# uart_izol.net
KiCad netlist of a schematic drawn in EAGLE
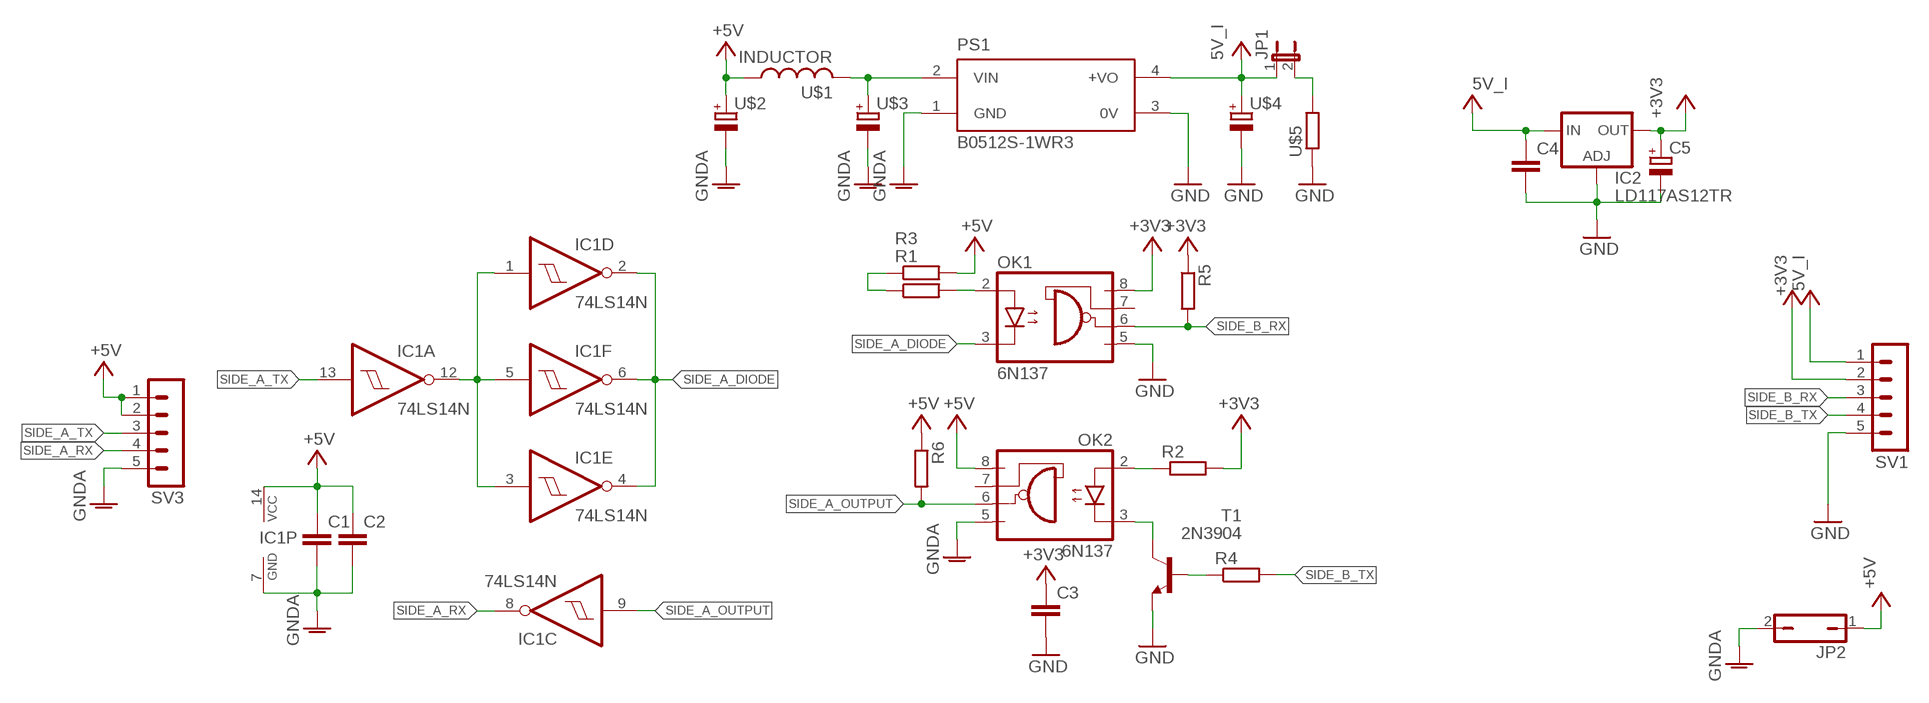
[diagram p0: schematic, sheet 1]

(export (version "E")
  (design (tool "Eeschema 10.0.6"))
  (components
    (comp (ref "C1")
      (value "C-EUC0805")
      (footprint "eagle-import:C0805")
      (libsource (lib "eagle-import") (part "C-EUC0805"))
    )
    (comp (ref "C2")
      (value "C-EUC0805")
      (footprint "eagle-import:C0805")
      (libsource (lib "eagle-import") (part "C-EUC0805"))
    )
    (comp (ref "C3")
      (value "C-EUC0805")
      (footprint "eagle-import:C0805")
      (libsource (lib "eagle-import") (part "C-EUC0805"))
    )
    (comp (ref "C4")
      (value "C-EUC0805")
      (footprint "eagle-import:C0805")
      (libsource (lib "eagle-import") (part "C-EUC0805"))
    )
    (comp (ref "C5")
      (value "CPOL-EUSMCB")
      (footprint "eagle-import:SMC_B")
      (libsource (lib "eagle-import") (part "CPOL-EUSMCB"))
    )
    (comp (ref "IC1")
      (value "74LS14N")
      (footprint "eagle-import:DIL14")
      (libsource (lib "eagle-import") (part "7414NLS"))
    )
    (comp (ref "IC2")
      (value "LD117AS12TR")
      (footprint "eagle-import:SOT223")
      (libsource (lib "eagle-import") (part "LD117A?S12TR"))
    )
    (comp (ref "JP1")
      (value "JP1E")
      (footprint "eagle-import:JP1")
      (libsource (lib "eagle-import") (part "JP1E"))
    )
    (comp (ref "JP2")
      (value "JP1Q")
      (footprint "eagle-import:JP1")
      (libsource (lib "eagle-import") (part "JP1Q"))
    )
    (comp (ref "OK1")
      (value "6N137")
      (footprint "eagle-import:DIL08")
      (libsource (lib "eagle-import") (part "6N137"))
    )
    (comp (ref "OK2")
      (value "6N137")
      (footprint "eagle-import:DIL08")
      (libsource (lib "eagle-import") (part "6N137"))
    )
    (comp (ref "PS1")
      (value "B0512S-1WR3")
      (footprint "eagle-import:CONV_B0512S-1WR3")
      (fields (field (name "MF") "Mornsun America, LLC"))
      (libsource (lib "eagle-import") (part "B0512S-1WR3"))
    )
    (comp (ref "R1")
      (value "R-EU_M0805")
      (footprint "eagle-import:M0805")
      (libsource (lib "eagle-import") (part "R-EU_M0805"))
    )
    (comp (ref "R2")
      (value "R-EU_M0805")
      (footprint "eagle-import:M0805")
      (libsource (lib "eagle-import") (part "R-EU_M0805"))
    )
    (comp (ref "R3")
      (value "R-EU_M0805")
      (footprint "eagle-import:M0805")
      (libsource (lib "eagle-import") (part "R-EU_M0805"))
    )
    (comp (ref "R4")
      (value "R-EU_M0805")
      (footprint "eagle-import:M0805")
      (libsource (lib "eagle-import") (part "R-EU_M0805"))
    )
    (comp (ref "R5")
      (value "R-EU_M0805")
      (footprint "eagle-import:M0805")
      (libsource (lib "eagle-import") (part "R-EU_M0805"))
    )
    (comp (ref "R6")
      (value "R-EU_M0805")
      (footprint "eagle-import:M0805")
      (libsource (lib "eagle-import") (part "R-EU_M0805"))
    )
    (comp (ref "SV1")
      (value "MA05-1")
      (footprint "eagle-import:MA05-1")
      (libsource (lib "eagle-import") (part "MA05-1"))
    )
    (comp (ref "SV3")
      (value "MA05-1")
      (footprint "eagle-import:MA05-1")
      (libsource (lib "eagle-import") (part "MA05-1"))
    )
    (comp (ref "T1")
      (value "2N3904")
      (footprint "eagle-import:TO92")
      (libsource (lib "eagle-import") (part "2N3904"))
    )
    (comp (ref "U$1")
      (value "INDUCTOR")
      (footprint "eagle-import:0207_10")
      (libsource (lib "eagle-import") (part "INDUCTOR"))
    )
    (comp (ref "U$2")
      (value "CAPACITOR")
      (footprint "eagle-import:E2,5-7")
      (libsource (lib "eagle-import") (part "CAPACITOR"))
    )
    (comp (ref "U$3")
      (value "CAPACITOR")
      (footprint "eagle-import:E2,5-7")
      (libsource (lib "eagle-import") (part "CAPACITOR"))
    )
    (comp (ref "U$4")
      (value "CAPACITOR")
      (footprint "eagle-import:E2,5-7")
      (libsource (lib "eagle-import") (part "CAPACITOR"))
    )
    (comp (ref "U$5")
      (value "RESISTOR")
      (footprint "eagle-import:0207_10")
      (libsource (lib "eagle-import") (part "RESISTOR"))
    )
  )
  (nets
    (net (code "1") (name "+3V3") (class "Default")
      (node (ref "C3") (pin "1") (pinfunction "1_1") (pintype "passive"))
      (node (ref "C5") (pin "+") (pinfunction "+_+") (pintype "passive"))
      (node (ref "IC2") (pin "4") (pinfunction "OUT_4") (pintype "passive"))
      (node (ref "OK1") (pin "8") (pinfunction "VCC_8") (pintype "passive"))
      (node (ref "R2") (pin "2") (pinfunction "2_2") (pintype "passive"))
      (node (ref "R5") (pin "1") (pinfunction "1_1") (pintype "passive"))
      (node (ref "SV1") (pin "2") (pinfunction "2_2") (pintype "passive"))
    )
    (net (code "2") (name "+5V") (class "Default")
      (node (ref "C1") (pin "1") (pinfunction "1_1") (pintype "passive"))
      (node (ref "C2") (pin "1") (pinfunction "1_1") (pintype "passive"))
      (node (ref "IC1") (pin "14") (pinfunction "VCC_14") (pintype "power_in"))
      (node (ref "JP2") (pin "1") (pinfunction "1_1") (pintype "passive"))
      (node (ref "OK2") (pin "8") (pinfunction "VCC_8") (pintype "passive"))
      (node (ref "R3") (pin "2") (pinfunction "2_2") (pintype "passive"))
      (node (ref "R6") (pin "1") (pinfunction "1_1") (pintype "passive"))
      (node (ref "SV3") (pin "1") (pinfunction "1_1") (pintype "passive"))
      (node (ref "SV3") (pin "2") (pinfunction "2_2") (pintype "passive"))
      (node (ref "U$1") (pin "1") (pinfunction "1_1") (pintype "passive"))
      (node (ref "U$2") (pin "+") (pinfunction "+_+") (pintype "passive"))
    )
    (net (code "3") (name "5V_I") (class "Default")
      (node (ref "C4") (pin "1") (pinfunction "1_1") (pintype "passive"))
      (node (ref "IC2") (pin "3") (pinfunction "IN_3") (pintype "input"))
      (node (ref "JP1") (pin "1") (pinfunction "1_1") (pintype "passive"))
      (node (ref "PS1") (pin "4") (pinfunction "+VO_4") (pintype "output"))
      (node (ref "SV1") (pin "1") (pinfunction "1_1") (pintype "passive"))
      (node (ref "U$4") (pin "+") (pinfunction "+_+") (pintype "passive"))
    )
    (net (code "4") (name "GND") (class "Default")
      (node (ref "C3") (pin "2") (pinfunction "2_2") (pintype "passive"))
      (node (ref "C4") (pin "2") (pinfunction "2_2") (pintype "passive"))
      (node (ref "C5") (pin "-") (pinfunction "-_-") (pintype "passive"))
      (node (ref "IC2") (pin "1") (pinfunction "ADJ_1") (pintype "input"))
      (node (ref "OK1") (pin "5") (pinfunction "GND_5") (pintype "passive"))
      (node (ref "PS1") (pin "3") (pinfunction "0V_3") (pintype "passive"))
      (node (ref "SV1") (pin "5") (pinfunction "5_5") (pintype "passive"))
      (node (ref "T1") (pin "3") (pinfunction "E_3") (pintype "passive"))
      (node (ref "U$4") (pin "-") (pinfunction "-_-") (pintype "passive"))
      (node (ref "U$5") (pin "1") (pinfunction "1_1") (pintype "passive"))
    )
    (net (code "5") (name "GNDA") (class "Default")
      (node (ref "C1") (pin "2") (pinfunction "2_2") (pintype "passive"))
      (node (ref "C2") (pin "2") (pinfunction "2_2") (pintype "passive"))
      (node (ref "IC1") (pin "7") (pinfunction "GND_7") (pintype "power_in"))
      (node (ref "JP2") (pin "2") (pinfunction "2_2") (pintype "passive"))
      (node (ref "OK2") (pin "5") (pinfunction "GND_5") (pintype "passive"))
      (node (ref "PS1") (pin "1") (pinfunction "GND_1") (pintype "power_in"))
      (node (ref "SV3") (pin "5") (pinfunction "5_5") (pintype "passive"))
      (node (ref "U$2") (pin "-") (pinfunction "-_-") (pintype "passive"))
      (node (ref "U$3") (pin "-") (pinfunction "-_-") (pintype "passive"))
    )
    (net (code "6") (name "Net-(IC1A-O)") (class "Default")
      (node (ref "IC1") (pin "1") (pinfunction "I_1") (pintype "input"))
      (node (ref "IC1") (pin "12") (pinfunction "O_12") (pintype "output"))
      (node (ref "IC1") (pin "3") (pinfunction "I_3") (pintype "input"))
      (node (ref "IC1") (pin "5") (pinfunction "I_5") (pintype "input"))
    )
    (net (code "7") (name "Net-(JP1-Pad2)") (class "Default")
      (node (ref "JP1") (pin "2") (pinfunction "2_2") (pintype "passive"))
      (node (ref "U$5") (pin "2") (pinfunction "2_2") (pintype "passive"))
    )
    (net (code "8") (name "Net-(OK1-A)") (class "Default")
      (node (ref "OK1") (pin "2") (pinfunction "A_2") (pintype "passive"))
      (node (ref "R1") (pin "2") (pinfunction "2_2") (pintype "passive"))
    )
    (net (code "9") (name "Net-(OK2-A)") (class "Default")
      (node (ref "OK2") (pin "2") (pinfunction "A_2") (pintype "passive"))
      (node (ref "R2") (pin "1") (pinfunction "1_1") (pintype "passive"))
    )
    (net (code "10") (name "Net-(OK2-C)") (class "Default")
      (node (ref "OK2") (pin "3") (pinfunction "C_3") (pintype "passive"))
      (node (ref "T1") (pin "1") (pinfunction "C_1") (pintype "passive"))
    )
    (net (code "11") (name "Net-(PS1-VIN)") (class "Default")
      (node (ref "PS1") (pin "2") (pinfunction "VIN_2") (pintype "input"))
      (node (ref "U$1") (pin "2") (pinfunction "2_2") (pintype "passive"))
      (node (ref "U$3") (pin "+") (pinfunction "+_+") (pintype "passive"))
    )
    (net (code "12") (name "Net-(R1-Pad1)") (class "Default")
      (node (ref "R1") (pin "1") (pinfunction "1_1") (pintype "passive"))
      (node (ref "R3") (pin "1") (pinfunction "1_1") (pintype "passive"))
    )
    (net (code "13") (name "Net-(T1-B)") (class "Default")
      (node (ref "R4") (pin "1") (pinfunction "1_1") (pintype "passive"))
      (node (ref "T1") (pin "2") (pinfunction "B_2") (pintype "passive"))
    )
    (net (code "14") (name "SIDE_A_DIODE") (class "Default")
      (node (ref "IC1") (pin "2") (pinfunction "O_2") (pintype "output"))
      (node (ref "IC1") (pin "4") (pinfunction "O_4") (pintype "output"))
      (node (ref "IC1") (pin "6") (pinfunction "O_6") (pintype "output"))
      (node (ref "OK1") (pin "3") (pinfunction "C_3") (pintype "passive"))
    )
    (net (code "15") (name "SIDE_A_OUTPUT") (class "Default")
      (node (ref "IC1") (pin "9") (pinfunction "I_9") (pintype "input"))
      (node (ref "OK2") (pin "6") (pinfunction "VO_6") (pintype "passive"))
      (node (ref "R6") (pin "2") (pinfunction "2_2") (pintype "passive"))
    )
    (net (code "16") (name "SIDE_A_RX") (class "Default")
      (node (ref "IC1") (pin "8") (pinfunction "O_8") (pintype "output"))
      (node (ref "SV3") (pin "4") (pinfunction "4_4") (pintype "passive"))
    )
    (net (code "17") (name "SIDE_A_TX") (class "Default")
      (node (ref "IC1") (pin "13") (pinfunction "I_13") (pintype "input"))
      (node (ref "SV3") (pin "3") (pinfunction "3_3") (pintype "passive"))
    )
    (net (code "18") (name "SIDE_B_RX") (class "Default")
      (node (ref "OK1") (pin "6") (pinfunction "VO_6") (pintype "passive"))
      (node (ref "R5") (pin "2") (pinfunction "2_2") (pintype "passive"))
      (node (ref "SV1") (pin "3") (pinfunction "3_3") (pintype "passive"))
    )
    (net (code "19") (name "SIDE_B_TX") (class "Default")
      (node (ref "R4") (pin "2") (pinfunction "2_2") (pintype "passive"))
      (node (ref "SV1") (pin "4") (pinfunction "4_4") (pintype "passive"))
    )
    (net (code "20") (name "unconnected-(OK1-VE-Pad7)") (class "Default")
      (node (ref "OK1") (pin "7") (pinfunction "VE_7") (pintype "passive"))
    )
    (net (code "21") (name "unconnected-(OK2-VE-Pad7)") (class "Default")
      (node (ref "OK2") (pin "7") (pinfunction "VE_7") (pintype "passive"))
    )
  )
)
